# Sheet1.net
KiCad netlist of a schematic drawn in Altium Designer
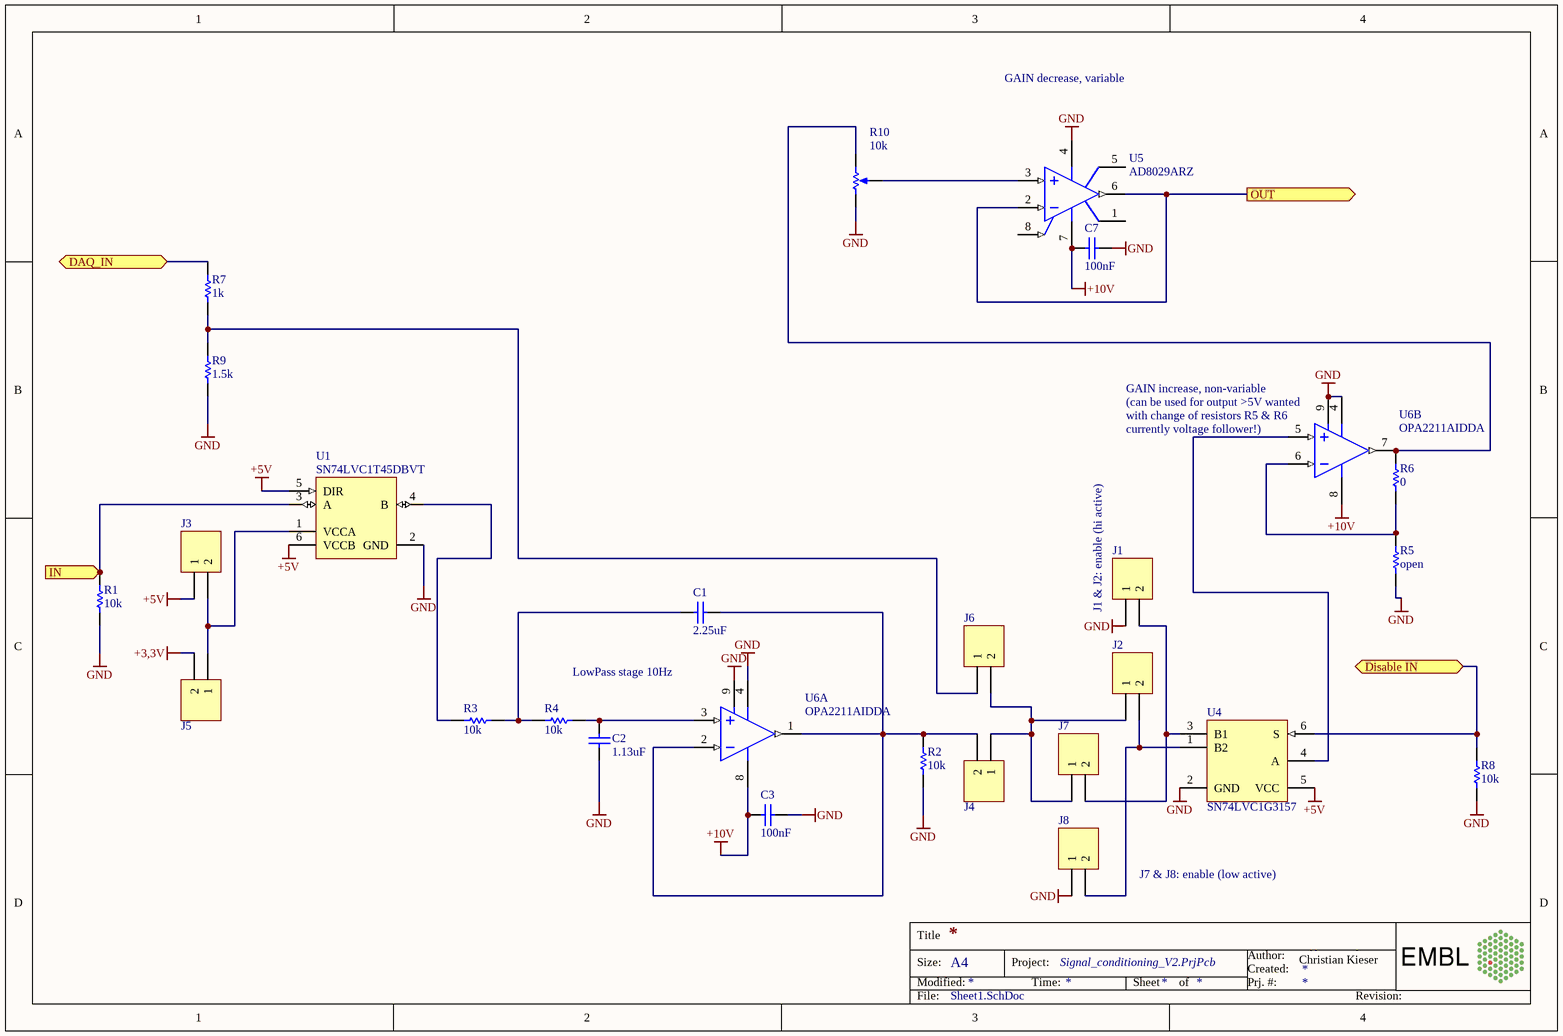
[diagram p0: Sheet1.SchDoc]

(export (version "E")
  (design (tool "Eeschema 10.0.6"))
  (components
    (comp (ref "C1")
      (value "2.25uF")
      (footprint "CAPC1206(3216)190_N")
      (description "CAP CER 1UF 10V X7R 1206")
      (fields
        (field (name "MANUFACTURER") "Wurth Electronics Inc.")
        (field (name "MANUFACTURER PART NUMBER") "885012208013")
      )
      (libsource (lib "Altium Vault EMBL 3") (part "CMP-001-0138-A.1"))
    )
    (comp (ref "C2")
      (value "1.13uF")
      (footprint "CAPC1206(3216)190_N")
      (description "CAP CER 1UF 10V X7R 1206")
      (fields
        (field (name "MANUFACTURER") "Wurth Electronics Inc.")
        (field (name "MANUFACTURER PART NUMBER") "885012208013")
      )
      (libsource (lib "Altium Vault EMBL 3") (part "CMP-001-0138-A.1"))
    )
    (comp (ref "C3")
      (value "100nF")
      (footprint "CAPC2013X88X50ML20T25")
      (description "generic 0805 COG oder X7R Vielschichtkondensatoren max. +/-10%")
      (libsource (lib "Altium Vault EMBL") (part "CMP-001-0082-2"))
    )
    (comp (ref "C7")
      (value "100nF")
      (footprint "CAPC2013X88X50ML20T25")
      (description "generic 0805 COG oder X7R Vielschichtkondensatoren max. +/-10%")
      (libsource (lib "Altium Vault EMBL 3") (part "CMP-001-0082-2"))
    )
    (comp (ref "J1")
      (value "61300211121")
      (footprint "61300211121")
      (description "2Pol; gerade; WR-PHD 2.54 mm THT Pin Header")
      (fields (field (name "MANUFACTURER") "Wurth Electronics"))
      (libsource (lib "Altium Vault EMBL 3") (part "CMP-001-0071-1"))
    )
    (comp (ref "J2")
      (value "61300211121")
      (footprint "61300211121")
      (description "2Pol; gerade; WR-PHD 2.54 mm THT Pin Header")
      (fields (field (name "MANUFACTURER") "Wurth Electronics"))
      (libsource (lib "Altium Vault EMBL 3") (part "CMP-001-0071-1"))
    )
    (comp (ref "J3")
      (value "61300211121")
      (footprint "61300211121")
      (description "2Pol; gerade; WR-PHD 2.54 mm THT Pin Header")
      (fields (field (name "MANUFACTURER") "Wurth Electronics"))
      (libsource (lib "Altium Vault EMBL 3") (part "CMP-001-0071-1"))
    )
    (comp (ref "J4")
      (value "61300211121")
      (footprint "61300211121")
      (description "2Pol; gerade; WR-PHD 2.54 mm THT Pin Header")
      (fields (field (name "MANUFACTURER") "Wurth Electronics"))
      (libsource (lib "") (part "CMP-001-0071-1_1"))
    )
    (comp (ref "J5")
      (value "61300211121")
      (footprint "61300211121")
      (description "2Pol; gerade; WR-PHD 2.54 mm THT Pin Header")
      (fields (field (name "MANUFACTURER") "Wurth Electronics"))
      (libsource (lib "") (part "CMP-001-0071-1_1"))
    )
    (comp (ref "J6")
      (value "61300211121")
      (footprint "61300211121")
      (description "2Pol; gerade; WR-PHD 2.54 mm THT Pin Header")
      (fields (field (name "MANUFACTURER") "Wurth Electronics"))
      (libsource (lib "Altium Vault EMBL 3") (part "CMP-001-0071-1"))
    )
    (comp (ref "J7")
      (value "61300211121")
      (footprint "61300211121")
      (description "2Pol; gerade; WR-PHD 2.54 mm THT Pin Header")
      (fields (field (name "MANUFACTURER") "Wurth Electronics"))
      (libsource (lib "Altium Vault EMBL 3") (part "CMP-001-0071-1"))
    )
    (comp (ref "J8")
      (value "61300211121")
      (footprint "61300211121")
      (description "2Pol; gerade; WR-PHD 2.54 mm THT Pin Header")
      (fields (field (name "MANUFACTURER") "Wurth Electronics"))
      (libsource (lib "Altium Vault EMBL 3") (part "CMP-001-0071-1"))
    )
    (comp (ref "R1")
      (value "10k")
      (footprint "YAGO-RC0805_M")
      (description "0805 Yageo Standard BlackBox Resistors")
      (fields (field (name "TOLERANCE") "±1%") (field (name "MANUFACTURER") "Yageo"))
      (libsource (lib "Altium Vault EMBL") (part "CMP-001-0027-2"))
    )
    (comp (ref "R2")
      (value "10k")
      (footprint "YAGO-RC0805_M")
      (description "0805 Yageo Standard BlackBox Resistors")
      (fields (field (name "TOLERANCE") "±1%") (field (name "MANUFACTURER") "Yageo"))
      (libsource (lib "Altium Vault EMBL") (part "CMP-001-0027-2"))
    )
    (comp (ref "R3")
      (value "10k")
      (footprint "YAGO-RC0805_M")
      (description "0805 Yageo Standard BlackBox Resistors")
      (fields (field (name "TOLERANCE") "±1%") (field (name "MANUFACTURER") "Yageo"))
      (libsource (lib "Altium Vault EMBL") (part "CMP-001-0027-2"))
    )
    (comp (ref "R4")
      (value "10k")
      (footprint "YAGO-RC0805_M")
      (description "0805 Yageo Standard BlackBox Resistors")
      (fields (field (name "TOLERANCE") "±1%") (field (name "MANUFACTURER") "Yageo"))
      (libsource (lib "Altium Vault EMBL") (part "CMP-001-0027-2"))
    )
    (comp (ref "R5")
      (value "open")
      (footprint "YAGO-RC0805_M")
      (description "0805 Yageo Standard BlackBox Resistors")
      (fields (field (name "TOLERANCE") "±1%") (field (name "MANUFACTURER") "Yageo"))
      (libsource (lib "Altium Vault EMBL 3") (part "CMP-001-0027-2"))
    )
    (comp (ref "R6")
      (value "0")
      (footprint "YAGO-RC0805_M")
      (description "0805 Yageo Standard BlackBox Resistors")
      (fields (field (name "TOLERANCE") "±1%") (field (name "MANUFACTURER") "Yageo"))
      (libsource (lib "Altium Vault EMBL 3") (part "CMP-001-0027-2"))
    )
    (comp (ref "R7")
      (value "1k")
      (footprint "YAGO-RC0805_M")
      (description "0805 Yageo Standard BlackBox Resistors")
      (fields (field (name "TOLERANCE") "±1%") (field (name "MANUFACTURER") "Yageo"))
      (libsource (lib "Altium Vault EMBL 3") (part "CMP-001-0027-2"))
    )
    (comp (ref "R8")
      (value "10k")
      (footprint "YAGO-RC0805_M")
      (description "0805 Yageo Standard BlackBox Resistors")
      (fields (field (name "TOLERANCE") "±1%") (field (name "MANUFACTURER") "Yageo"))
      (libsource (lib "Altium Vault EMBL") (part "CMP-001-0027-2"))
    )
    (comp (ref "R9")
      (value "1.5k")
      (footprint "YAGO-RC0805_M")
      (description "0805 Yageo Standard BlackBox Resistors")
      (fields (field (name "TOLERANCE") "±1%") (field (name "MANUFACTURER") "Yageo"))
      (libsource (lib "Altium Vault EMBL 3") (part "CMP-001-0027-2"))
    )
    (comp (ref "R10")
      (value "10k")
      (footprint "Typ 3362P")
      (description "Trimmer_stehend_quadratisch_Verstellung-von-oben")
      (fields
        (field (name "MANUFACTURER") "Bourns Inc.")
        (field (name "MANUFACTURER PART NUMBER") "3362P-1-103LF")
      )
      (libsource (lib "Altium Vault EMBL 3") (part "CMP-001-0077-3"))
    )
    (comp (ref "U1")
      (value "SN74LVC1T45DBVT")
      (footprint "DBV0006A_M")
      (fields
        (field (name "MANUFACTURER") "Texas Instruments")
        (field (name "GENERIC PART NUMBER") "SN74LVC1T45")
      )
      (libsource (lib "Altium Vault EMBL 3") (part "CMP-00491-1"))
    )
    (comp (ref "U4")
      (value "SN74LVC1G3157")
      (footprint "DBV0006A_N")
      (description "Analoger Schalter Single SPDT(Wechsler) SOT23-6")
      (fields
        (field (name "MANUFACTURER") "Texas Instruments")
        (field (name "MANUFACTURER PART NUMBER") "74LVC1G3157DBVRE4")
      )
      (libsource (lib "Altium Vault EMBL 3") (part "CMP-001-0106-A.1"))
    )
    (comp (ref "U5")
      (value "AD8029ARZ")
      (footprint "ADI-R-8_L")
      (fields (field (name "MANUFACTURER") "Analog Devices") (field (name "GENERIC PART NUMBER") "AD8029"))
      (libsource (lib "Altium Vault EMBL 3") (part "CMP-00480-1"))
    )
    (comp (ref "U6")
      (value "OPA2211AIDDA")
      (footprint "DDA0008C_M")
      (fields (field (name "MANUFACTURER") "Texas Instruments"))
      (libsource (lib "Altium Vault EMBL 3") (part "CMP-00511-1"))
    )
  )
  (nets
    (net (code "1") (name "+3,3V") (class "Default")
      (node (ref "J5") (pin "2") (pinfunction "2_2") (pintype "passive"))
    )
    (net (code "2") (name "+5V") (class "Default")
      (node (ref "J3") (pin "1") (pinfunction "1_1") (pintype "passive"))
      (node (ref "U1") (pin "5") (pinfunction "DIR_5") (pintype "input"))
      (node (ref "U1") (pin "6") (pinfunction "VCCB_6") (pintype "power_in"))
      (node (ref "U4") (pin "5") (pinfunction "VCC_5") (pintype "power_in"))
    )
    (net (code "3") (name "+10V") (class "Default")
      (node (ref "C3") (pin "2") (pinfunction "2_2") (pintype "passive"))
      (node (ref "C7") (pin "2") (pinfunction "2_2") (pintype "passive"))
      (node (ref "U5") (pin "7") (pinfunction "+VS_7") (pintype "power_in"))
      (node (ref "U6") (pin "8") (pinfunction "V+_8") (pintype "power_in"))
    )
    (net (code "4") (name "/DAQ_IN") (class "Default")
      (node (ref "R7") (pin "2") (pinfunction "2_2") (pintype "passive"))
    )
    (net (code "5") (name "/Disable IN") (class "Default")
      (node (ref "R8") (pin "1") (pinfunction "1_1") (pintype "passive"))
      (node (ref "U4") (pin "6") (pinfunction "S_6") (pintype "input"))
    )
    (net (code "6") (name "/IN") (class "Default")
      (node (ref "R1") (pin "2") (pinfunction "2_2") (pintype "passive"))
      (node (ref "U1") (pin "3") (pinfunction "A_3") (pintype "bidirectional"))
    )
    (net (code "7") (name "/OUT") (class "Default")
      (node (ref "U5") (pin "2") (pinfunction "-IN_2") (pintype "input"))
      (node (ref "U5") (pin "6") (pinfunction "VOUT_6") (pintype "output"))
    )
    (net (code "8") (name "GND") (class "Default")
      (node (ref "C2") (pin "1") (pinfunction "1_1") (pintype "passive"))
      (node (ref "C3") (pin "1") (pinfunction "1_1") (pintype "passive"))
      (node (ref "C7") (pin "1") (pinfunction "1_1") (pintype "passive"))
      (node (ref "J1") (pin "1") (pinfunction "1_1") (pintype "passive"))
      (node (ref "J8") (pin "1") (pinfunction "1_1") (pintype "passive"))
      (node (ref "R1") (pin "1") (pinfunction "1_1") (pintype "passive"))
      (node (ref "R10") (pin "1") (pinfunction "CCW_1") (pintype "passive"))
      (node (ref "R2") (pin "1") (pinfunction "1_1") (pintype "passive"))
      (node (ref "R5") (pin "1") (pinfunction "1_1") (pintype "passive"))
      (node (ref "R8") (pin "2") (pinfunction "2_2") (pintype "passive"))
      (node (ref "R9") (pin "1") (pinfunction "1_1") (pintype "passive"))
      (node (ref "U1") (pin "2") (pinfunction "GND_2") (pintype "power_in"))
      (node (ref "U4") (pin "2") (pinfunction "GND_2") (pintype "power_in"))
      (node (ref "U5") (pin "4") (pinfunction "-VS_4") (pintype "power_in"))
      (node (ref "U6") (pin "4") (pinfunction "V-_4") (pintype "power_in"))
      (node (ref "U6") (pin "9") (pinfunction "EP_9") (pintype "power_in"))
    )
    (net (code "9") (name "Net-(C1-Pad1)") (class "Default")
      (node (ref "C1") (pin "1") (pinfunction "1_1") (pintype "passive"))
      (node (ref "R3") (pin "1") (pinfunction "1_1") (pintype "passive"))
      (node (ref "R4") (pin "2") (pinfunction "2_2") (pintype "passive"))
    )
    (net (code "10") (name "Net-(J2-Pad1)") (class "Default")
      (node (ref "J2") (pin "1") (pinfunction "1_1") (pintype "passive"))
      (node (ref "J4") (pin "1") (pinfunction "1_1") (pintype "passive"))
      (node (ref "J6") (pin "2") (pinfunction "2_2") (pintype "passive"))
      (node (ref "J7") (pin "1") (pinfunction "1_1") (pintype "passive"))
    )
    (net (code "11") (name "Net-(J6-Pad1)") (class "Default")
      (node (ref "J6") (pin "1") (pinfunction "1_1") (pintype "passive"))
      (node (ref "R7") (pin "1") (pinfunction "1_1") (pintype "passive"))
      (node (ref "R9") (pin "2") (pinfunction "2_2") (pintype "passive"))
    )
    (net (code "12") (name "Net-(R10-CW)") (class "Default")
      (node (ref "R10") (pin "3") (pinfunction "CW_3") (pintype "passive"))
      (node (ref "R6") (pin "2") (pinfunction "2_2") (pintype "passive"))
      (node (ref "U6") (pin "7") (pinfunction "OUT_B_7") (pintype "output"))
    )
    (net (code "13") (name "Net-(R10-S)") (class "Default")
      (node (ref "R10") (pin "2") (pinfunction "S_2") (pintype "passive"))
      (node (ref "U5") (pin "3") (pinfunction "+IN_3") (pintype "input"))
    )
    (net (code "14") (name "Net-(U1-B)") (class "Default")
      (node (ref "R3") (pin "2") (pinfunction "2_2") (pintype "passive"))
      (node (ref "U1") (pin "4") (pinfunction "B_4") (pintype "bidirectional"))
    )
    (net (code "15") (name "Net-(U1-VCCA)") (class "Default")
      (node (ref "J3") (pin "2") (pinfunction "2_2") (pintype "passive"))
      (node (ref "J5") (pin "1") (pinfunction "1_1") (pintype "passive"))
      (node (ref "U1") (pin "1") (pinfunction "VCCA_1") (pintype "power_in"))
    )
    (net (code "16") (name "Net-(U4-A)") (class "Default")
      (node (ref "U4") (pin "4") (pinfunction "A_4") (pintype "passive"))
      (node (ref "U6") (pin "5") (pinfunction "IN_B+_5") (pintype "input"))
    )
    (net (code "17") (name "Net-(U4-B1)") (class "Default")
      (node (ref "J1") (pin "2") (pinfunction "2_2") (pintype "passive"))
      (node (ref "J7") (pin "2") (pinfunction "2_2") (pintype "passive"))
      (node (ref "U4") (pin "3") (pinfunction "B1_3") (pintype "passive"))
    )
    (net (code "18") (name "Net-(U4-B2)") (class "Default")
      (node (ref "J2") (pin "2") (pinfunction "2_2") (pintype "passive"))
      (node (ref "J8") (pin "2") (pinfunction "2_2") (pintype "passive"))
      (node (ref "U4") (pin "1") (pinfunction "B2_1") (pintype "passive"))
    )
    (net (code "19") (name "Net-(U6A-IN_A+)") (class "Default")
      (node (ref "C2") (pin "2") (pinfunction "2_2") (pintype "passive"))
      (node (ref "R4") (pin "1") (pinfunction "1_1") (pintype "passive"))
      (node (ref "U6") (pin "3") (pinfunction "IN_A+_3") (pintype "input"))
    )
    (net (code "20") (name "Net-(U6A-IN_A-)") (class "Default")
      (node (ref "C1") (pin "2") (pinfunction "2_2") (pintype "passive"))
      (node (ref "J4") (pin "2") (pinfunction "2_2") (pintype "passive"))
      (node (ref "R2") (pin "2") (pinfunction "2_2") (pintype "passive"))
      (node (ref "U6") (pin "1") (pinfunction "OUT_A_1") (pintype "output"))
      (node (ref "U6") (pin "2") (pinfunction "IN_A-_2") (pintype "input"))
    )
    (net (code "21") (name "Net-(U6B-IN_B-)") (class "Default")
      (node (ref "R5") (pin "2") (pinfunction "2_2") (pintype "passive"))
      (node (ref "R6") (pin "1") (pinfunction "1_1") (pintype "passive"))
      (node (ref "U6") (pin "6") (pinfunction "IN_B-_6") (pintype "input"))
    )
    (net (code "22") (name "unconnected-(U5-NC-Pad1)") (class "Default")
      (node (ref "U5") (pin "1") (pinfunction "NC_1") (pintype "passive"))
    )
    (net (code "23") (name "unconnected-(U5-NC-Pad5)") (class "Default")
      (node (ref "U5") (pin "5") (pinfunction "NC_5") (pintype "passive"))
    )
    (net (code "24") (name "unconnected-(U5-~{DISABLE}-Pad8)") (class "Default")
      (node (ref "U5") (pin "8") (pinfunction "~{DISABLE}_8") (pintype "input"))
    )
  )
)
